# ARM_SERVO.net
KiCad netlist of a schematic drawn in Altium Designer
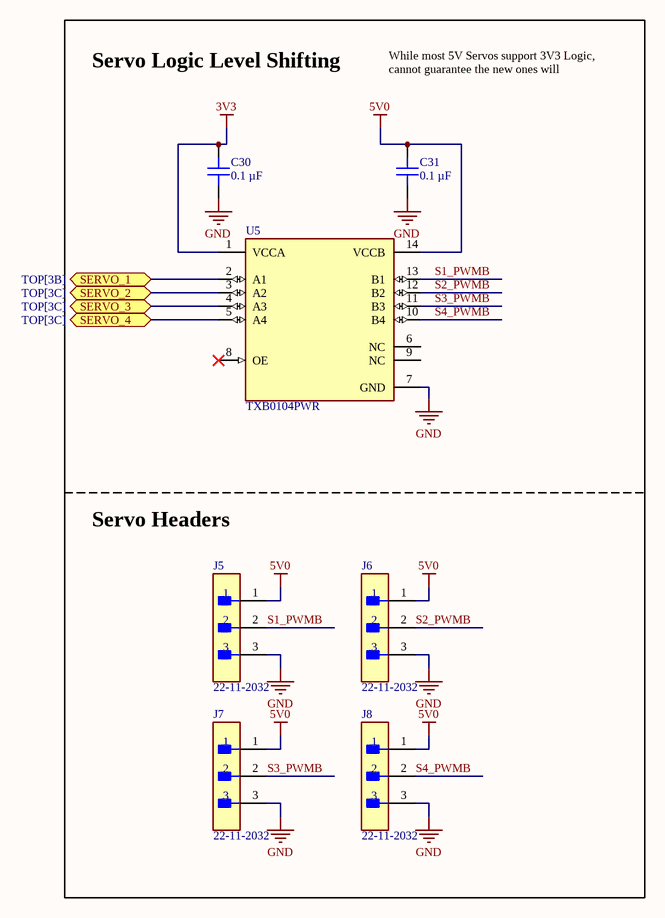
[diagram p0: ARM_SERVO.SchDoc]

(export (version "E")
  (design (tool "Eeschema 10.0.6"))
  (components
    (comp (ref "C30")
      (value "0.1 µF")
      (footprint "CAP 0603_1608")
      (description "CAP0603 X7R .1UF 10% 25V")
      (fields
        (field (name "PART NUMBER") "GMC10X7R104K25NT")
        (field (name "MANUFACTURER") "Cal-Chip Electronics, Inc.")
      )
      (libsource (lib "Celestial Altium Library - altium_library") (part "Capacitor"))
    )
    (comp (ref "C31")
      (value "0.1 µF")
      (footprint "CAP 0603_1608")
      (description "CAP0603 X7R .1UF 10% 25V")
      (fields
        (field (name "PART NUMBER") "GMC10X7R104K25NT")
        (field (name "MANUFACTURER") "Cal-Chip Electronics, Inc.")
      )
      (libsource (lib "Celestial Altium Library - altium_library") (part "Capacitor"))
    )
    (comp (ref "J5")
      (value "22-11-2032")
      (footprint "FP-22-11-2032-MFG")
      (description "CONN HEADER VERT 3POS 2.54MM")
      (fields
        (field (name "MANUFACTURER") "Molex")
        (field (name "OCTOPART") "https://octopart.com/22-11-2032-molex-10085")
      )
      (libsource (lib "Altium Content Vault") (part "0d3f023dd272f625e17a2be33dea85f"))
    )
    (comp (ref "J6")
      (value "22-11-2032")
      (footprint "FP-22-11-2032-MFG")
      (description "CONN HEADER VERT 3POS 2.54MM")
      (fields
        (field (name "MANUFACTURER") "Molex")
        (field (name "OCTOPART") "https://octopart.com/22-11-2032-molex-10085")
      )
      (libsource (lib "Altium Content Vault") (part "0d3f023dd272f625e17a2be33dea85f"))
    )
    (comp (ref "J7")
      (value "22-11-2032")
      (footprint "FP-22-11-2032-MFG")
      (description "CONN HEADER VERT 3POS 2.54MM")
      (fields
        (field (name "MANUFACTURER") "Molex")
        (field (name "OCTOPART") "https://octopart.com/22-11-2032-molex-10085")
      )
      (libsource (lib "Altium Content Vault") (part "0d3f023dd272f625e17a2be33dea85f"))
    )
    (comp (ref "J8")
      (value "22-11-2032")
      (footprint "FP-22-11-2032-MFG")
      (description "CONN HEADER VERT 3POS 2.54MM")
      (fields
        (field (name "MANUFACTURER") "Molex")
        (field (name "OCTOPART") "https://octopart.com/22-11-2032-molex-10085")
      )
      (libsource (lib "Altium Content Vault") (part "0d3f023dd272f625e17a2be33dea85f"))
    )
    (comp (ref "U5")
      (value "TXB0104PWR")
      (footprint "Texas_Instruments_PW0014A_MFG")
      (libsource (lib "Altium Content Vault") (part "TXB0104PWR"))
    )
  )
  (nets
    (net (code "1") (name "/S1_PWMB") (class "Default")
      (node (ref "J5") (pin "2") (pinfunction "2_2") (pintype "passive"))
      (node (ref "U5") (pin "13") (pinfunction "B1_13") (pintype "bidirectional"))
    )
    (net (code "2") (name "/S2_PWMB") (class "Default")
      (node (ref "J6") (pin "2") (pinfunction "2_2") (pintype "passive"))
      (node (ref "U5") (pin "12") (pinfunction "B2_12") (pintype "bidirectional"))
    )
    (net (code "3") (name "/S3_PWMB") (class "Default")
      (node (ref "J7") (pin "2") (pinfunction "2_2") (pintype "passive"))
      (node (ref "U5") (pin "11") (pinfunction "B3_11") (pintype "bidirectional"))
    )
    (net (code "4") (name "/S4_PWMB") (class "Default")
      (node (ref "J8") (pin "2") (pinfunction "2_2") (pintype "passive"))
      (node (ref "U5") (pin "10") (pinfunction "B4_10") (pintype "bidirectional"))
    )
    (net (code "5") (name "/SERVO_1") (class "Default")
      (node (ref "U5") (pin "2") (pinfunction "A1_2") (pintype "bidirectional"))
    )
    (net (code "6") (name "/SERVO_2") (class "Default")
      (node (ref "U5") (pin "3") (pinfunction "A2_3") (pintype "bidirectional"))
    )
    (net (code "7") (name "/SERVO_3") (class "Default")
      (node (ref "U5") (pin "4") (pinfunction "A3_4") (pintype "bidirectional"))
    )
    (net (code "8") (name "/SERVO_4") (class "Default")
      (node (ref "U5") (pin "5") (pinfunction "A4_5") (pintype "bidirectional"))
    )
    (net (code "9") (name "3V3") (class "Default")
      (node (ref "C30") (pin "2") (pinfunction "2_2") (pintype "passive"))
      (node (ref "U5") (pin "1") (pinfunction "VCCA_1") (pintype "power_in"))
    )
    (net (code "10") (name "5V0") (class "Default")
      (node (ref "C31") (pin "2") (pinfunction "2_2") (pintype "passive"))
      (node (ref "J5") (pin "1") (pinfunction "1_1") (pintype "passive"))
      (node (ref "J6") (pin "1") (pinfunction "1_1") (pintype "passive"))
      (node (ref "J7") (pin "1") (pinfunction "1_1") (pintype "passive"))
      (node (ref "J8") (pin "1") (pinfunction "1_1") (pintype "passive"))
      (node (ref "U5") (pin "14") (pinfunction "VCCB_14") (pintype "power_in"))
    )
    (net (code "11") (name "GND") (class "Default")
      (node (ref "C30") (pin "1") (pinfunction "1_1") (pintype "passive"))
      (node (ref "C31") (pin "1") (pinfunction "1_1") (pintype "passive"))
      (node (ref "J5") (pin "3") (pinfunction "3_3") (pintype "passive"))
      (node (ref "J6") (pin "3") (pinfunction "3_3") (pintype "passive"))
      (node (ref "J7") (pin "3") (pinfunction "3_3") (pintype "passive"))
      (node (ref "J8") (pin "3") (pinfunction "3_3") (pintype "passive"))
      (node (ref "U5") (pin "7") (pinfunction "GND_7") (pintype "power_in"))
    )
    (net (code "12") (name "unconnected-(U5-NC-Pad6)") (class "Default")
      (node (ref "U5") (pin "6") (pinfunction "NC_6") (pintype "passive"))
    )
    (net (code "13") (name "unconnected-(U5-NC-Pad9)") (class "Default")
      (node (ref "U5") (pin "9") (pinfunction "NC_9") (pintype "passive"))
    )
    (net (code "14") (name "unconnected-(U5-OE-Pad8)") (class "Default")
      (node (ref "U5") (pin "8") (pinfunction "OE_8") (pintype "input+no_connect"))
    )
  )
)
